# avr_pong.net
KiCad netlist of a schematic drawn in EAGLE
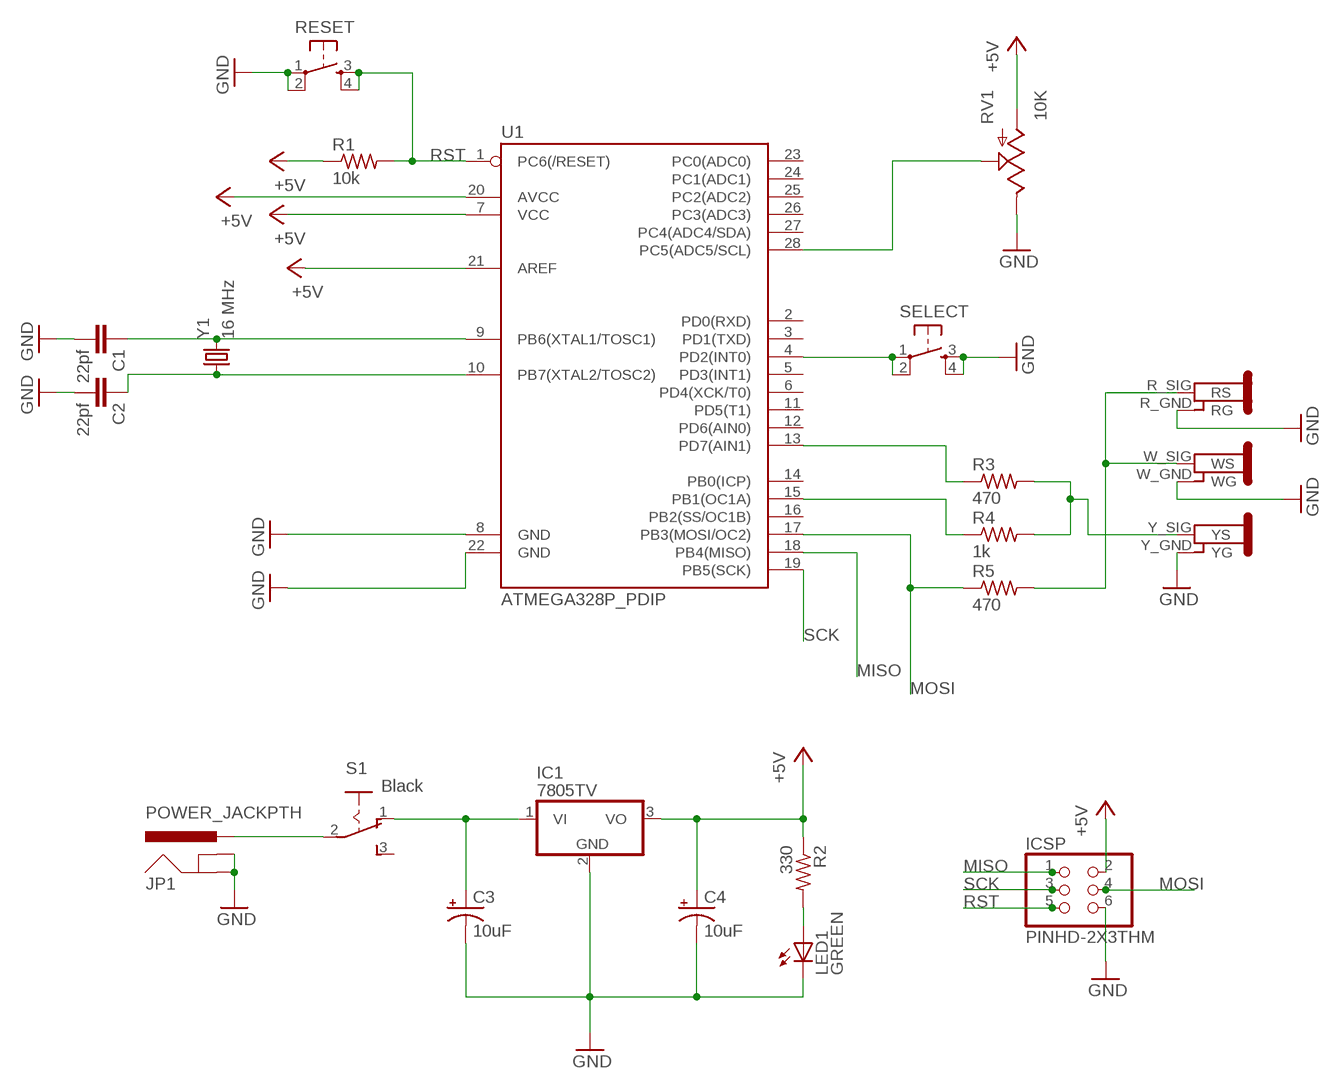
[diagram p0: schematic, sheet 1]

(export (version "E")
  (design (tool "Eeschema 10.0.6"))
  (components
    (comp (ref "C1")
      (value "22pf")
      (footprint "eagle-import:CAP-PTH-SMALL-KIT")
      (libsource (lib "eagle-import") (part "CAPKIT"))
    )
    (comp (ref "C2")
      (value "22pf")
      (footprint "eagle-import:CAP-PTH-SMALL-KIT")
      (libsource (lib "eagle-import") (part "CAPKIT"))
    )
    (comp (ref "C3")
      (value "10uF")
      (footprint "eagle-import:E2,5-5")
      (libsource (lib "eagle-import") (part "CPOL-USE2.5-5"))
    )
    (comp (ref "C4")
      (value "10uF")
      (footprint "eagle-import:E2,5-5")
      (libsource (lib "eagle-import") (part "CPOL-USE2.5-5"))
    )
    (comp (ref "IC1")
      (value "7805TV")
      (footprint "eagle-import:TO220V")
      (libsource (lib "eagle-import") (part "78TV05"))
    )
    (comp (ref "ICSP")
      (value "PINHD-2X3THM")
      (footprint "eagle-import:ISP6")
      (libsource (lib "eagle-import") (part "PINHD-2X3THM"))
    )
    (comp (ref "JP1")
      (value "POWER_JACKPTH")
      (footprint "eagle-import:POWER_JACK_PTH")
      (libsource (lib "eagle-import") (part "POWER_JACKPTH"))
    )
    (comp (ref "LED1")
      (value "GREEN")
      (footprint "eagle-import:LED5MM")
      (libsource (lib "eagle-import") (part "LED5MM"))
    )
    (comp (ref "R1")
      (value "10k")
      (footprint "eagle-import:0207_10")
      (libsource (lib "eagle-import") (part "R-US_0207/10"))
    )
    (comp (ref "R2")
      (value "330")
      (footprint "eagle-import:0207_10")
      (libsource (lib "eagle-import") (part "R-US_0207/10"))
    )
    (comp (ref "R3")
      (value "470")
      (footprint "eagle-import:0207_10")
      (libsource (lib "eagle-import") (part "R-US_0207/10"))
    )
    (comp (ref "R4")
      (value "1k")
      (footprint "eagle-import:0207_10")
      (libsource (lib "eagle-import") (part "R-US_0207/10"))
    )
    (comp (ref "R5")
      (value "470")
      (footprint "eagle-import:0207_10")
      (libsource (lib "eagle-import") (part "R-US_0207/10"))
    )
    (comp (ref "RESET")
      (value "TACTILE-SWITCH-PTH")
      (footprint "eagle-import:TAC-SWITCH-PTH")
      (libsource (lib "eagle-import") (part "TACTILE-SWITCH-PTH"))
    )
    (comp (ref "RV1")
      (value "10K")
      (footprint "eagle-import:POT_ALPHA_RV16AF-20")
      (libsource (lib "eagle-import") (part "POT-RV16AF-20"))
    )
    (comp (ref "S1")
      (value "Black")
      (footprint "eagle-import:M251")
      (libsource (lib "eagle-import") (part "M251"))
    )
    (comp (ref "SELECT")
      (value "TACTILE-SWITCH-PTH")
      (footprint "eagle-import:TAC-SWITCH-PTH")
      (libsource (lib "eagle-import") (part "TACTILE-SWITCH-PTH"))
    )
    (comp (ref "U$1")
      (value "3-RCA-JACK")
      (footprint "eagle-import:3-RCA-JACK")
      (libsource (lib "eagle-import") (part "3-RCA-JACK"))
    )
    (comp (ref "U1")
      (value "ATMEGA328P_PDIP")
      (footprint "eagle-import:DIL28-3")
      (libsource (lib "eagle-import") (part "ATMEGA328P_PDIP"))
    )
    (comp (ref "Y1")
      (value "16 MHz")
      (footprint "eagle-import:HC49US")
      (libsource (lib "eagle-import") (part "CRYSTALHC49US"))
    )
  )
  (nets
    (net (code "1") (name "+5V") (class "Default")
      (node (ref "C4") (pin "+") (pinfunction "+_+") (pintype "passive"))
      (node (ref "IC1") (pin "3") (pinfunction "VO_3") (pintype "passive"))
      (node (ref "ICSP") (pin "2") (pinfunction "2_2") (pintype "passive"))
      (node (ref "R1") (pin "1") (pinfunction "1_1") (pintype "passive"))
      (node (ref "R2") (pin "1") (pinfunction "1_1") (pintype "passive"))
      (node (ref "RV1") (pin "1") (pinfunction "A_1") (pintype "passive"))
      (node (ref "U1") (pin "20") (pinfunction "AVCC_20") (pintype "bidirectional"))
      (node (ref "U1") (pin "21") (pinfunction "AREF_21") (pintype "bidirectional"))
      (node (ref "U1") (pin "7") (pinfunction "VCC_7") (pintype "bidirectional"))
    )
    (net (code "2") (name "/MISO") (class "Default")
      (node (ref "ICSP") (pin "1") (pinfunction "1_1") (pintype "passive"))
      (node (ref "U1") (pin "18") (pinfunction "PB4(MISO)_18") (pintype "bidirectional"))
    )
    (net (code "3") (name "/MOSI") (class "Default")
      (node (ref "ICSP") (pin "4") (pinfunction "4_4") (pintype "passive"))
      (node (ref "R5") (pin "1") (pinfunction "1_1") (pintype "passive"))
      (node (ref "U1") (pin "17") (pinfunction "PB3(MOSI/OC2)_17") (pintype "bidirectional"))
    )
    (net (code "4") (name "/RST") (class "Default")
      (node (ref "ICSP") (pin "5") (pinfunction "5_5") (pintype "passive"))
      (node (ref "R1") (pin "2") (pinfunction "2_2") (pintype "passive"))
      (node (ref "RESET") (pin "3") (pinfunction "3_3") (pintype "passive"))
      (node (ref "RESET") (pin "4") (pinfunction "4_4") (pintype "passive"))
      (node (ref "U1") (pin "1") (pinfunction "PC6(/RESET)_1") (pintype "bidirectional"))
    )
    (net (code "5") (name "/SCK") (class "Default")
      (node (ref "ICSP") (pin "3") (pinfunction "3_3") (pintype "passive"))
      (node (ref "U1") (pin "19") (pinfunction "PB5(SCK)_19") (pintype "bidirectional"))
    )
    (net (code "6") (name "GND") (class "Default")
      (node (ref "C1") (pin "2") (pinfunction "2_2") (pintype "passive"))
      (node (ref "C2") (pin "2") (pinfunction "2_2") (pintype "passive"))
      (node (ref "C3") (pin "-") (pinfunction "-_-") (pintype "passive"))
      (node (ref "C4") (pin "-") (pinfunction "-_-") (pintype "passive"))
      (node (ref "IC1") (pin "2") (pinfunction "GND_2") (pintype "passive"))
      (node (ref "ICSP") (pin "6") (pinfunction "6_6") (pintype "passive"))
      (node (ref "JP1") (pin "GND") (pinfunction "GND_GND") (pintype "bidirectional"))
      (node (ref "JP1") (pin "GNDBREAK") (pinfunction "GNDBREAK_GNDBREAK") (pintype "bidirectional"))
      (node (ref "LED1") (pin "K") (pinfunction "C_K") (pintype "passive"))
      (node (ref "RESET") (pin "1") (pinfunction "1_1") (pintype "passive"))
      (node (ref "RESET") (pin "2") (pinfunction "2_2") (pintype "passive"))
      (node (ref "RV1") (pin "3") (pinfunction "E_3") (pintype "passive"))
      (node (ref "SELECT") (pin "3") (pinfunction "3_3") (pintype "passive"))
      (node (ref "SELECT") (pin "4") (pinfunction "4_4") (pintype "passive"))
      (node (ref "U$1") (pin "R_GND") (pinfunction "RG_R_GND") (pintype "bidirectional"))
      (node (ref "U$1") (pin "W_GND") (pinfunction "WG_W_GND") (pintype "bidirectional"))
      (node (ref "U$1") (pin "Y_GND") (pinfunction "YG_Y_GND") (pintype "bidirectional"))
      (node (ref "U1") (pin "22") (pinfunction "GND_22") (pintype "bidirectional"))
      (node (ref "U1") (pin "8") (pinfunction "GND_8") (pintype "bidirectional"))
    )
    (net (code "7") (name "Net-(IC1-VI)") (class "Default")
      (node (ref "C3") (pin "+") (pinfunction "+_+") (pintype "passive"))
      (node (ref "IC1") (pin "1") (pinfunction "VI_1") (pintype "input"))
      (node (ref "S1") (pin "1") (pinfunction "O_1") (pintype "passive"))
    )
    (net (code "8") (name "Net-(LED1-PadA)") (class "Default")
      (node (ref "LED1") (pin "A") (pinfunction "A_A") (pintype "passive"))
      (node (ref "R2") (pin "2") (pinfunction "2_2") (pintype "passive"))
    )
    (net (code "9") (name "Net-(RV1-S)") (class "Default")
      (node (ref "RV1") (pin "2") (pinfunction "S_2") (pintype "passive"))
      (node (ref "U1") (pin "28") (pinfunction "PC5(ADC5/SCL)_28") (pintype "bidirectional"))
    )
    (net (code "10") (name "Net-(S1-P)") (class "Default")
      (node (ref "JP1") (pin "PWR") (pinfunction "PWR_PWR") (pintype "bidirectional"))
      (node (ref "S1") (pin "2") (pinfunction "P_2") (pintype "passive"))
    )
    (net (code "11") (name "Net-(U$1-RS)") (class "Default")
      (node (ref "R5") (pin "2") (pinfunction "2_2") (pintype "passive"))
      (node (ref "U$1") (pin "R_SIG") (pinfunction "RS_R_SIG") (pintype "bidirectional"))
      (node (ref "U$1") (pin "W_SIG") (pinfunction "WS_W_SIG") (pintype "bidirectional"))
    )
    (net (code "12") (name "Net-(U$1-YS)") (class "Default")
      (node (ref "R3") (pin "2") (pinfunction "2_2") (pintype "passive"))
      (node (ref "R4") (pin "2") (pinfunction "2_2") (pintype "passive"))
      (node (ref "U$1") (pin "Y_SIG") (pinfunction "YS_Y_SIG") (pintype "bidirectional"))
    )
    (net (code "13") (name "Net-(U1-PB1(OC1A))") (class "Default")
      (node (ref "R4") (pin "1") (pinfunction "1_1") (pintype "passive"))
      (node (ref "U1") (pin "15") (pinfunction "PB1(OC1A)_15") (pintype "bidirectional"))
    )
    (net (code "14") (name "Net-(U1-PB6(XTAL1{slash}TOSC1))") (class "Default")
      (node (ref "C1") (pin "1") (pinfunction "1_1") (pintype "passive"))
      (node (ref "U1") (pin "9") (pinfunction "PB6(XTAL1/TOSC1)_9") (pintype "bidirectional"))
      (node (ref "Y1") (pin "2") (pinfunction "2_2") (pintype "passive"))
    )
    (net (code "15") (name "Net-(U1-PB7(XTAL2{slash}TOSC2))") (class "Default")
      (node (ref "C2") (pin "1") (pinfunction "1_1") (pintype "passive"))
      (node (ref "U1") (pin "10") (pinfunction "PB7(XTAL2/TOSC2)_10") (pintype "bidirectional"))
      (node (ref "Y1") (pin "1") (pinfunction "1_1") (pintype "passive"))
    )
    (net (code "16") (name "Net-(U1-PD2(INT0))") (class "Default")
      (node (ref "SELECT") (pin "1") (pinfunction "1_1") (pintype "passive"))
      (node (ref "SELECT") (pin "2") (pinfunction "2_2") (pintype "passive"))
      (node (ref "U1") (pin "4") (pinfunction "PD2(INT0)_4") (pintype "bidirectional"))
    )
    (net (code "17") (name "Net-(U1-PD7(AIN1))") (class "Default")
      (node (ref "R3") (pin "1") (pinfunction "1_1") (pintype "passive"))
      (node (ref "U1") (pin "13") (pinfunction "PD7(AIN1)_13") (pintype "bidirectional"))
    )
    (net (code "18") (name "unconnected-(S1-S-Pad3)") (class "Default")
      (node (ref "S1") (pin "3") (pinfunction "S_3") (pintype "passive"))
    )
    (net (code "19") (name "unconnected-(U1-PB0(ICP)-Pad14)") (class "Default")
      (node (ref "U1") (pin "14") (pinfunction "PB0(ICP)_14") (pintype "bidirectional"))
    )
    (net (code "20") (name "unconnected-(U1-PB2(SS{slash}OC1B)-Pad16)") (class "Default")
      (node (ref "U1") (pin "16") (pinfunction "PB2(SS/OC1B)_16") (pintype "bidirectional"))
    )
    (net (code "21") (name "unconnected-(U1-PC0(ADC0)-Pad23)") (class "Default")
      (node (ref "U1") (pin "23") (pinfunction "PC0(ADC0)_23") (pintype "bidirectional"))
    )
    (net (code "22") (name "unconnected-(U1-PC1(ADC1)-Pad24)") (class "Default")
      (node (ref "U1") (pin "24") (pinfunction "PC1(ADC1)_24") (pintype "bidirectional"))
    )
    (net (code "23") (name "unconnected-(U1-PC2(ADC2)-Pad25)") (class "Default")
      (node (ref "U1") (pin "25") (pinfunction "PC2(ADC2)_25") (pintype "bidirectional"))
    )
    (net (code "24") (name "unconnected-(U1-PC3(ADC3)-Pad26)") (class "Default")
      (node (ref "U1") (pin "26") (pinfunction "PC3(ADC3)_26") (pintype "bidirectional"))
    )
    (net (code "25") (name "unconnected-(U1-PC4(ADC4{slash}SDA)-Pad27)") (class "Default")
      (node (ref "U1") (pin "27") (pinfunction "PC4(ADC4/SDA)_27") (pintype "bidirectional"))
    )
    (net (code "26") (name "unconnected-(U1-PD0(RXD)-Pad2)") (class "Default")
      (node (ref "U1") (pin "2") (pinfunction "PD0(RXD)_2") (pintype "bidirectional"))
    )
    (net (code "27") (name "unconnected-(U1-PD1(TXD)-Pad3)") (class "Default")
      (node (ref "U1") (pin "3") (pinfunction "PD1(TXD)_3") (pintype "bidirectional"))
    )
    (net (code "28") (name "unconnected-(U1-PD3(INT1)-Pad5)") (class "Default")
      (node (ref "U1") (pin "5") (pinfunction "PD3(INT1)_5") (pintype "bidirectional"))
    )
    (net (code "29") (name "unconnected-(U1-PD4(XCK{slash}T0)-Pad6)") (class "Default")
      (node (ref "U1") (pin "6") (pinfunction "PD4(XCK/T0)_6") (pintype "bidirectional"))
    )
    (net (code "30") (name "unconnected-(U1-PD5(T1)-Pad11)") (class "Default")
      (node (ref "U1") (pin "11") (pinfunction "PD5(T1)_11") (pintype "bidirectional"))
    )
    (net (code "31") (name "unconnected-(U1-PD6(AIN0)-Pad12)") (class "Default")
      (node (ref "U1") (pin "12") (pinfunction "PD6(AIN0)_12") (pintype "bidirectional"))
    )
  )
)
